# lna_simple.net
KiCad netlist of a schematic drawn in EAGLE
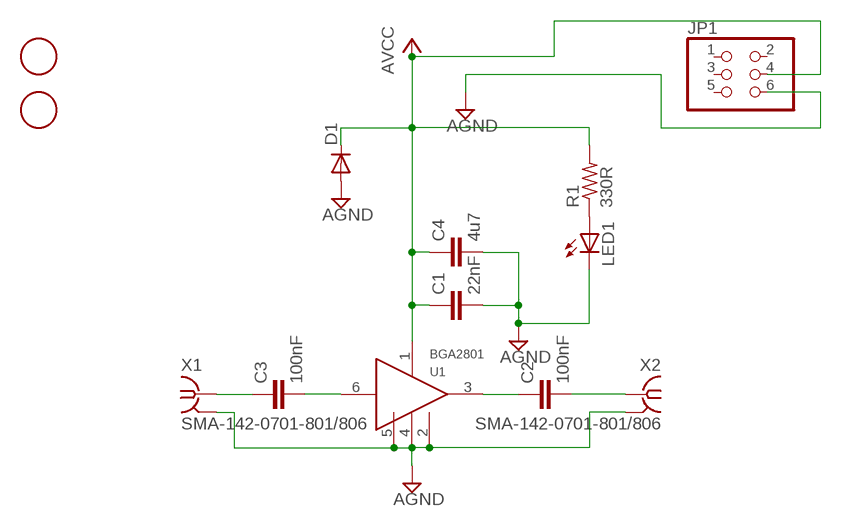
[diagram p0: schematic, sheet 1]

(export (version "E")
  (design (tool "Eeschema 10.0.6"))
  (components
    (comp (ref "C1")
      (value "22nF")
      (footprint "eagle-import:C0603")
      (libsource (lib "eagle-import") (part "C-EUC0603"))
    )
    (comp (ref "C2")
      (value "100nF")
      (footprint "eagle-import:C0603")
      (libsource (lib "eagle-import") (part "C-EUC0603"))
    )
    (comp (ref "C3")
      (value "100nF")
      (footprint "eagle-import:C0603")
      (libsource (lib "eagle-import") (part "C-EUC0603"))
    )
    (comp (ref "C4")
      (value "4u7")
      (footprint "eagle-import:C0805")
      (libsource (lib "eagle-import") (part "C-EUC0805"))
    )
    (comp (ref "D1")
      (value "DIODE-DO214AC")
      (footprint "eagle-import:DO214AC")
      (libsource (lib "eagle-import") (part "DIODE-DO214AC"))
    )
    (comp (ref "JP1")
      (value "PINHD-2X3")
      (footprint "eagle-import:2X03")
      (libsource (lib "eagle-import") (part "PINHD-2X3"))
    )
    (comp (ref "LED1")
      (value "LEDCHIP-LED0603")
      (footprint "eagle-import:CHIP-LED0603")
      (libsource (lib "eagle-import") (part "LEDCHIP-LED0603"))
    )
    (comp (ref "R1")
      (value "330R")
      (footprint "eagle-import:R0603")
      (libsource (lib "eagle-import") (part "R-US_R0603"))
    )
    (comp (ref "U$1")
      (value "FIDUCIAL")
      (footprint "eagle-import:FIDUCIAL_1MM")
      (libsource (lib "eagle-import") (part "FIDUCIAL"))
    )
    (comp (ref "U$2")
      (value "FIDUCIAL")
      (footprint "eagle-import:FIDUCIAL_1MM")
      (libsource (lib "eagle-import") (part "FIDUCIAL"))
    )
    (comp (ref "U1")
      (value "BGA2801")
      (footprint "eagle-import:SOTT323-6")
      (libsource (lib "eagle-import") (part "BGA2801"))
    )
    (comp (ref "X1")
      (value "SMA-142-0701-801/806")
      (footprint "eagle-import:J502-ND-142-0701-801_806")
      (fields (field (name "MF") "JOHNSON COMPONENTS") (field (name "MPN") "142-0701-801"))
      (libsource (lib "eagle-import") (part "SMA-142-0701-801/806"))
    )
    (comp (ref "X2")
      (value "SMA-142-0701-801/806")
      (footprint "eagle-import:J502-ND-142-0701-801_806")
      (fields (field (name "MF") "JOHNSON COMPONENTS") (field (name "MPN") "142-0701-801"))
      (libsource (lib "eagle-import") (part "SMA-142-0701-801/806"))
    )
  )
  (nets
    (net (code "1") (name "AGND") (class "Default")
      (node (ref "C1") (pin "2") (pinfunction "2_2") (pintype "passive"))
      (node (ref "C4") (pin "2") (pinfunction "2_2") (pintype "passive"))
      (node (ref "D1") (pin "A") (pinfunction "A_A") (pintype "passive"))
      (node (ref "JP1") (pin "6") (pinfunction "6_6") (pintype "passive"))
      (node (ref "LED1") (pin "C") (pinfunction "C_C") (pintype "passive"))
      (node (ref "U1") (pin "2") (pinfunction "GND_2") (pintype "bidirectional"))
      (node (ref "U1") (pin "4") (pinfunction "GND_4") (pintype "bidirectional"))
      (node (ref "U1") (pin "5") (pinfunction "GND_5") (pintype "bidirectional"))
      (node (ref "X1") (pin "G@1") (pinfunction "2_G@1") (pintype "passive"))
      (node (ref "X1") (pin "G@2") (pinfunction "2_G@2") (pintype "passive"))
      (node (ref "X1") (pin "G@3") (pinfunction "2_G@3") (pintype "passive"))
      (node (ref "X1") (pin "G@4") (pinfunction "2_G@4") (pintype "passive"))
      (node (ref "X2") (pin "G@1") (pinfunction "2_G@1") (pintype "passive"))
      (node (ref "X2") (pin "G@2") (pinfunction "2_G@2") (pintype "passive"))
      (node (ref "X2") (pin "G@3") (pinfunction "2_G@3") (pintype "passive"))
      (node (ref "X2") (pin "G@4") (pinfunction "2_G@4") (pintype "passive"))
    )
    (net (code "2") (name "AVCC") (class "Default")
      (node (ref "C1") (pin "1") (pinfunction "1_1") (pintype "passive"))
      (node (ref "C4") (pin "1") (pinfunction "1_1") (pintype "passive"))
      (node (ref "D1") (pin "C") (pinfunction "C_C") (pintype "passive"))
      (node (ref "JP1") (pin "4") (pinfunction "4_4") (pintype "passive"))
      (node (ref "R1") (pin "2") (pinfunction "2_2") (pintype "passive"))
      (node (ref "U1") (pin "1") (pinfunction "VCC_1") (pintype "bidirectional"))
    )
    (net (code "3") (name "Net-(C2-Pad2)") (class "Default")
      (node (ref "C2") (pin "2") (pinfunction "2_2") (pintype "passive"))
      (node (ref "X2") (pin "1") (pinfunction "1_1") (pintype "passive"))
    )
    (net (code "4") (name "Net-(C3-Pad1)") (class "Default")
      (node (ref "C3") (pin "1") (pinfunction "1_1") (pintype "passive"))
      (node (ref "X1") (pin "1") (pinfunction "1_1") (pintype "passive"))
    )
    (net (code "5") (name "Net-(LED1-PadA)") (class "Default")
      (node (ref "LED1") (pin "A") (pinfunction "A_A") (pintype "passive"))
      (node (ref "R1") (pin "1") (pinfunction "1_1") (pintype "passive"))
    )
    (net (code "6") (name "Net-(U1-IN)") (class "Default")
      (node (ref "C3") (pin "2") (pinfunction "2_2") (pintype "passive"))
      (node (ref "U1") (pin "6") (pinfunction "IN_6") (pintype "bidirectional"))
    )
    (net (code "7") (name "Net-(U1-OUT)") (class "Default")
      (node (ref "C2") (pin "1") (pinfunction "1_1") (pintype "passive"))
      (node (ref "U1") (pin "3") (pinfunction "OUT_3") (pintype "bidirectional"))
    )
    (net (code "8") (name "unconnected-(JP1-Pad1)") (class "Default")
      (node (ref "JP1") (pin "1") (pinfunction "1_1") (pintype "passive"))
    )
    (net (code "9") (name "unconnected-(JP1-Pad2)") (class "Default")
      (node (ref "JP1") (pin "2") (pinfunction "2_2") (pintype "passive"))
    )
    (net (code "10") (name "unconnected-(JP1-Pad3)") (class "Default")
      (node (ref "JP1") (pin "3") (pinfunction "3_3") (pintype "passive"))
    )
    (net (code "11") (name "unconnected-(JP1-Pad5)") (class "Default")
      (node (ref "JP1") (pin "5") (pinfunction "5_5") (pintype "passive"))
    )
  )
)
